# lm1117_out_5v.net
KiCad netlist of a schematic drawn in EAGLE
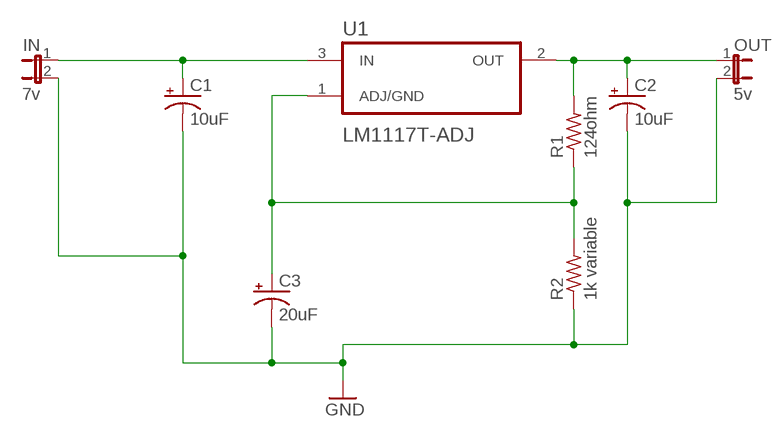
[diagram p0: schematic, sheet 1]

(export (version "E")
  (design (tool "Eeschema 10.0.6"))
  (components
    (comp (ref "C1")
      (value "10uF")
      (footprint "eagle-import:CT6032")
      (libsource (lib "eagle-import") (part "CPOL-USCT6032"))
    )
    (comp (ref "C2")
      (value "10uF")
      (footprint "eagle-import:CT6032")
      (libsource (lib "eagle-import") (part "CPOL-USCT6032"))
    )
    (comp (ref "C3")
      (value "20uF")
      (footprint "eagle-import:CT6032")
      (libsource (lib "eagle-import") (part "CPOL-USCT6032"))
    )
    (comp (ref "IN")
      (value "7v")
      (footprint "eagle-import:JP1")
      (libsource (lib "eagle-import") (part "JP1E"))
    )
    (comp (ref "OUT")
      (value "5v")
      (footprint "eagle-import:JP1")
      (libsource (lib "eagle-import") (part "JP1E"))
    )
    (comp (ref "R1")
      (value "124ohm")
      (footprint "eagle-import:0207_7")
      (libsource (lib "eagle-import") (part "R-US_0207/7"))
    )
    (comp (ref "R2")
      (value "1k variable")
      (footprint "eagle-import:0207_7")
      (libsource (lib "eagle-import") (part "R-US_0207/7"))
    )
    (comp (ref "U1")
      (value "LM1117T-ADJ")
      (footprint "eagle-import:TO254P1054X470X1955-3")
      (fields (field (name "MF") "Texas Instruments") (field (name "MP") "LM1117T-ADJ/NOPB"))
      (libsource (lib "eagle-import") (part "LM1117T-ADJ"))
    )
  )
  (nets
    (net (code "1") (name "GND") (class "Default")
      (node (ref "C1") (pin "-") (pinfunction "-_-") (pintype "passive"))
      (node (ref "C2") (pin "-") (pinfunction "-_-") (pintype "passive"))
      (node (ref "C3") (pin "-") (pinfunction "-_-") (pintype "passive"))
      (node (ref "IN") (pin "2") (pinfunction "2_2") (pintype "passive"))
      (node (ref "OUT") (pin "2") (pinfunction "2_2") (pintype "passive"))
      (node (ref "R2") (pin "1") (pinfunction "1_1") (pintype "passive"))
    )
    (net (code "2") (name "Net-(U1-ADJ{slash}GND)") (class "Default")
      (node (ref "C3") (pin "+") (pinfunction "+_+") (pintype "passive"))
      (node (ref "R1") (pin "1") (pinfunction "1_1") (pintype "passive"))
      (node (ref "R2") (pin "2") (pinfunction "2_2") (pintype "passive"))
      (node (ref "U1") (pin "1") (pinfunction "ADJ/GND_1") (pintype "bidirectional"))
    )
    (net (code "3") (name "Net-(U1-IN)") (class "Default")
      (node (ref "C1") (pin "+") (pinfunction "+_+") (pintype "passive"))
      (node (ref "IN") (pin "1") (pinfunction "1_1") (pintype "passive"))
      (node (ref "U1") (pin "3") (pinfunction "IN_3") (pintype "input"))
    )
    (net (code "4") (name "Net-(U1-OUT)") (class "Default")
      (node (ref "C2") (pin "+") (pinfunction "+_+") (pintype "passive"))
      (node (ref "OUT") (pin "1") (pinfunction "1_1") (pintype "passive"))
      (node (ref "R1") (pin "2") (pinfunction "2_2") (pintype "passive"))
      (node (ref "U1") (pin "2") (pinfunction "OUT_2") (pintype "output"))
    )
  )
)
